# PCB_6.net
KiCad netlist of a schematic drawn in EAGLE
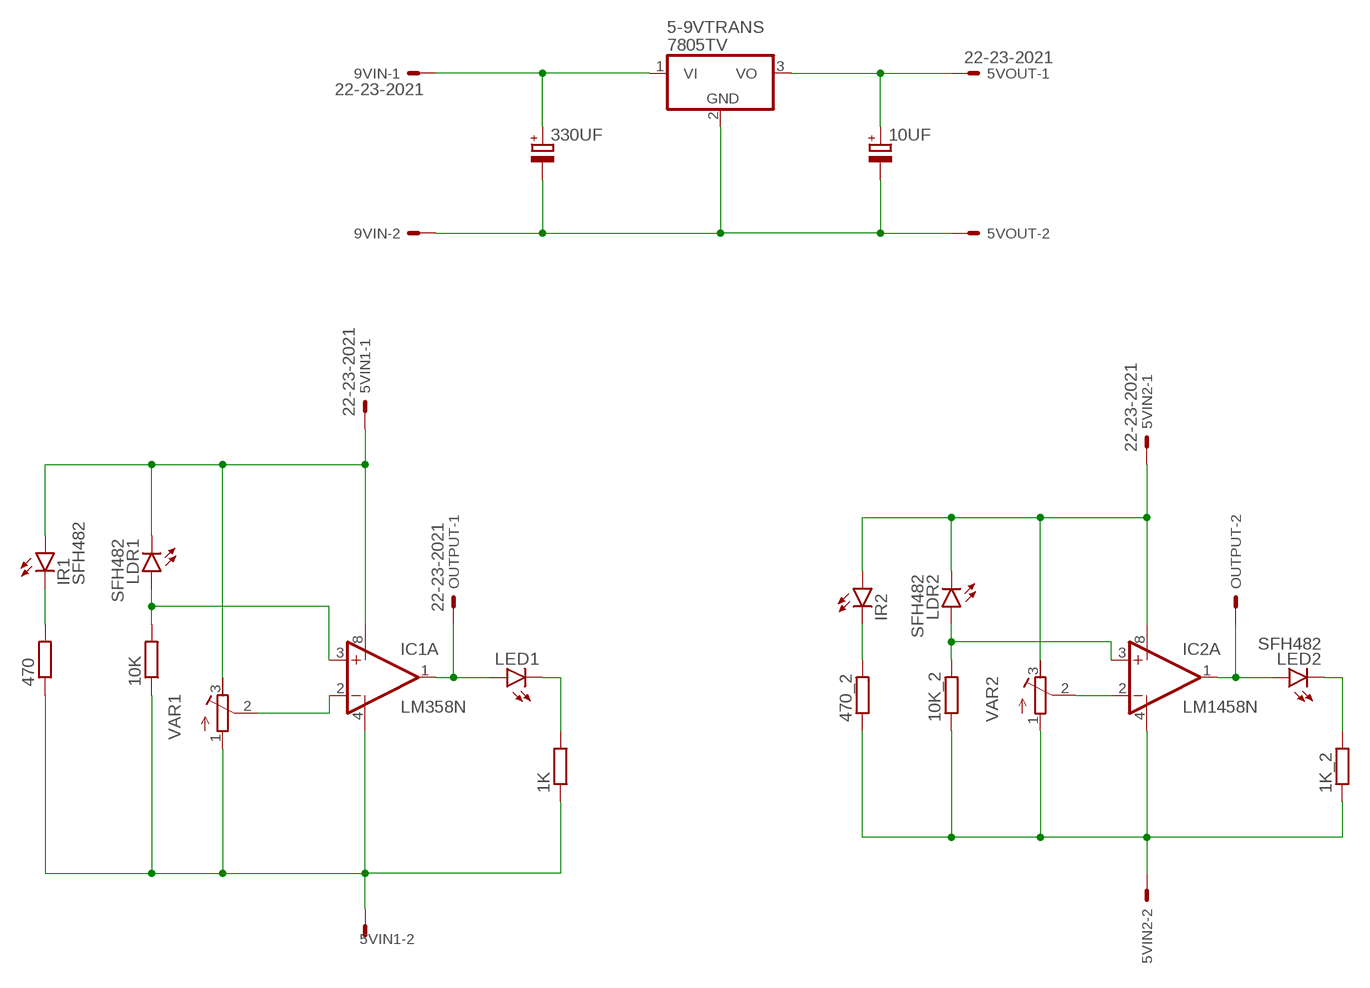
[diagram p0: schematic, sheet 1]

(export (version "E")
  (design (tool "Eeschema 10.0.6"))
  (components
    (comp (ref "1K")
      (value "R-EU_0207/10")
      (footprint "eagle-import:0207_10")
      (libsource (lib "eagle-import") (part "R-EU_0207/10"))
    )
    (comp (ref "1K_2")
      (value "R-EU_0207/10")
      (footprint "eagle-import:0207_10")
      (libsource (lib "eagle-import") (part "R-EU_0207/10"))
    )
    (comp (ref "5-9VTRANS")
      (value "7805TV")
      (footprint "eagle-import:TO220V")
      (libsource (lib "eagle-import") (part "78TV05"))
    )
    (comp (ref "5VIN1")
      (value "22-23-2021")
      (footprint "eagle-import:22-23-2021")
      (fields (field (name "MF") "MOLEX"))
      (libsource (lib "eagle-import") (part "22-23-2021"))
    )
    (comp (ref "5VIN2")
      (value "22-23-2021")
      (footprint "eagle-import:22-23-2021")
      (fields (field (name "MF") "MOLEX"))
      (libsource (lib "eagle-import") (part "22-23-2021"))
    )
    (comp (ref "5VOUT")
      (value "22-23-2021")
      (footprint "eagle-import:22-23-2021")
      (fields (field (name "MF") "MOLEX"))
      (libsource (lib "eagle-import") (part "22-23-2021"))
    )
    (comp (ref "9VIN")
      (value "22-23-2021")
      (footprint "eagle-import:22-23-2021")
      (fields (field (name "MF") "MOLEX"))
      (libsource (lib "eagle-import") (part "22-23-2021"))
    )
    (comp (ref "10K")
      (value "R-EU_0207/10")
      (footprint "eagle-import:0207_10")
      (libsource (lib "eagle-import") (part "R-EU_0207/10"))
    )
    (comp (ref "10K_2")
      (value "R-EU_0207/10")
      (footprint "eagle-import:0207_10")
      (libsource (lib "eagle-import") (part "R-EU_0207/10"))
    )
    (comp (ref "10UF")
      (value "CPOL-EUE1.8-4")
      (footprint "eagle-import:E1,8-4")
      (libsource (lib "eagle-import") (part "CPOL-EUE1.8-4"))
    )
    (comp (ref "330UF")
      (value "CPOL-EUE2,5-6E")
      (footprint "eagle-import:E2,5-6E")
      (libsource (lib "eagle-import") (part "CPOL-EUE2,5-6E"))
    )
    (comp (ref "470")
      (value "R-EU_0207/10")
      (footprint "eagle-import:0207_10")
      (libsource (lib "eagle-import") (part "R-EU_0207/10"))
    )
    (comp (ref "470_2")
      (value "R-EU_0207/10")
      (footprint "eagle-import:0207_10")
      (libsource (lib "eagle-import") (part "R-EU_0207/10"))
    )
    (comp (ref "IC1")
      (value "LM358N")
      (footprint "eagle-import:DIL08")
      (libsource (lib "eagle-import") (part "LM358N"))
    )
    (comp (ref "IC2")
      (value "LM1458N")
      (footprint "eagle-import:DIL08")
      (libsource (lib "eagle-import") (part "1458NLM"))
    )
    (comp (ref "IR1")
      (value "SFH482")
      (footprint "eagle-import:SFH482")
      (libsource (lib "eagle-import") (part "SFH482"))
    )
    (comp (ref "IR2")
      (value "LEDSFH480")
      (footprint "eagle-import:SFH480")
      (libsource (lib "eagle-import") (part "LEDSFH480"))
    )
    (comp (ref "LDR1")
      (value "SFH482")
      (footprint "eagle-import:SFH482")
      (libsource (lib "eagle-import") (part "SFH482"))
    )
    (comp (ref "LDR2")
      (value "SFH482")
      (footprint "eagle-import:SFH482")
      (libsource (lib "eagle-import") (part "SFH482"))
    )
    (comp (ref "LED1")
      (value "LEDSFH480")
      (footprint "eagle-import:SFH480")
      (libsource (lib "eagle-import") (part "LEDSFH480"))
    )
    (comp (ref "LED2")
      (value "SFH482")
      (footprint "eagle-import:SFH482")
      (libsource (lib "eagle-import") (part "SFH482"))
    )
    (comp (ref "OUTPUT")
      (value "22-23-2021")
      (footprint "eagle-import:22-23-2021")
      (fields (field (name "MF") "MOLEX"))
      (libsource (lib "eagle-import") (part "22-23-2021"))
    )
    (comp (ref "VAR1")
      (value "R-TRIMM64W")
      (footprint "eagle-import:RTRIM64W")
      (libsource (lib "eagle-import") (part "R-TRIMM64W"))
    )
    (comp (ref "VAR2")
      (value "R-TRIMM64W")
      (footprint "eagle-import:RTRIM64W")
      (libsource (lib "eagle-import") (part "R-TRIMM64W"))
    )
  )
  (nets
    (net (code "1") (name "Net-(5-9VTRANS-GND)") (class "Default")
      (node (ref "10UF") (pin "-") (pinfunction "-_-") (pintype "passive"))
      (node (ref "330UF") (pin "-") (pinfunction "-_-") (pintype "passive"))
      (node (ref "5-9VTRANS") (pin "2") (pinfunction "GND_2") (pintype "passive"))
      (node (ref "5VOUT") (pin "2") (pinfunction "S_2") (pintype "passive"))
      (node (ref "9VIN") (pin "2") (pinfunction "S_2") (pintype "passive"))
    )
    (net (code "2") (name "Net-(5-9VTRANS-VI)") (class "Default")
      (node (ref "330UF") (pin "+") (pinfunction "+_+") (pintype "passive"))
      (node (ref "5-9VTRANS") (pin "1") (pinfunction "VI_1") (pintype "input"))
      (node (ref "9VIN") (pin "1") (pinfunction "S_1") (pintype "passive"))
    )
    (net (code "3") (name "Net-(5-9VTRANS-VO)") (class "Default")
      (node (ref "10UF") (pin "+") (pinfunction "+_+") (pintype "passive"))
      (node (ref "5-9VTRANS") (pin "3") (pinfunction "VO_3") (pintype "passive"))
      (node (ref "5VOUT") (pin "1") (pinfunction "S_1") (pintype "passive"))
    )
    (net (code "4") (name "Net-(5VIN1A-S)") (class "Default")
      (node (ref "5VIN1") (pin "1") (pinfunction "S_1") (pintype "passive"))
      (node (ref "IC1") (pin "8") (pinfunction "V+_8") (pintype "power_in"))
      (node (ref "IR1") (pin "A") (pinfunction "A_A") (pintype "passive"))
      (node (ref "LDR1") (pin "K") (pinfunction "C_K") (pintype "passive"))
      (node (ref "VAR1") (pin "3") (pinfunction "E_3") (pintype "passive"))
    )
    (net (code "5") (name "Net-(5VIN1B-S)") (class "Default")
      (node (ref "10K") (pin "1") (pinfunction "1_1") (pintype "passive"))
      (node (ref "1K") (pin "1") (pinfunction "1_1") (pintype "passive"))
      (node (ref "470") (pin "1") (pinfunction "1_1") (pintype "passive"))
      (node (ref "5VIN1") (pin "2") (pinfunction "S_2") (pintype "passive"))
      (node (ref "IC1") (pin "4") (pinfunction "V-_4") (pintype "power_in"))
      (node (ref "VAR1") (pin "1") (pinfunction "A_1") (pintype "passive"))
    )
    (net (code "6") (name "Net-(5VIN2A-S)") (class "Default")
      (node (ref "5VIN2") (pin "1") (pinfunction "S_1") (pintype "passive"))
      (node (ref "IC2") (pin "8") (pinfunction "V+_8") (pintype "power_in"))
      (node (ref "IR2") (pin "A") (pinfunction "A_A") (pintype "passive"))
      (node (ref "LDR2") (pin "K") (pinfunction "C_K") (pintype "passive"))
      (node (ref "VAR2") (pin "3") (pinfunction "E_3") (pintype "passive"))
    )
    (net (code "7") (name "Net-(5VIN2B-S)") (class "Default")
      (node (ref "10K_2") (pin "1") (pinfunction "1_1") (pintype "passive"))
      (node (ref "1K_2") (pin "1") (pinfunction "1_1") (pintype "passive"))
      (node (ref "470_2") (pin "1") (pinfunction "1_1") (pintype "passive"))
      (node (ref "5VIN2") (pin "2") (pinfunction "S_2") (pintype "passive"))
      (node (ref "IC2") (pin "4") (pinfunction "V-_4") (pintype "power_in"))
      (node (ref "VAR2") (pin "1") (pinfunction "A_1") (pintype "passive"))
    )
    (net (code "8") (name "Net-(IC1A-+IN)") (class "Default")
      (node (ref "10K") (pin "2") (pinfunction "2_2") (pintype "passive"))
      (node (ref "IC1") (pin "3") (pinfunction "+IN_3") (pintype "input"))
      (node (ref "LDR1") (pin "A") (pinfunction "A_A") (pintype "passive"))
    )
    (net (code "9") (name "Net-(IC1A--IN)") (class "Default")
      (node (ref "IC1") (pin "2") (pinfunction "-IN_2") (pintype "input"))
      (node (ref "VAR1") (pin "2") (pinfunction "S_2") (pintype "passive"))
    )
    (net (code "10") (name "Net-(IC1A-OUT)") (class "Default")
      (node (ref "IC1") (pin "1") (pinfunction "OUT_1") (pintype "output"))
      (node (ref "LED1") (pin "A") (pinfunction "A_A") (pintype "passive"))
      (node (ref "OUTPUT") (pin "1") (pinfunction "S_1") (pintype "passive"))
    )
    (net (code "11") (name "Net-(IC2A-+IN)") (class "Default")
      (node (ref "10K_2") (pin "2") (pinfunction "2_2") (pintype "passive"))
      (node (ref "IC2") (pin "3") (pinfunction "+IN_3") (pintype "input"))
      (node (ref "LDR2") (pin "A") (pinfunction "A_A") (pintype "passive"))
    )
    (net (code "12") (name "Net-(IC2A--IN)") (class "Default")
      (node (ref "IC2") (pin "2") (pinfunction "-IN_2") (pintype "input"))
      (node (ref "VAR2") (pin "2") (pinfunction "S_2") (pintype "passive"))
    )
    (net (code "13") (name "Net-(IC2A-OUT)") (class "Default")
      (node (ref "IC2") (pin "1") (pinfunction "OUT_1") (pintype "output"))
      (node (ref "LED2") (pin "A") (pinfunction "A_A") (pintype "passive"))
      (node (ref "OUTPUT") (pin "2") (pinfunction "S_2") (pintype "passive"))
    )
    (net (code "14") (name "Net-(IR1-C)") (class "Default")
      (node (ref "470") (pin "2") (pinfunction "2_2") (pintype "passive"))
      (node (ref "IR1") (pin "K") (pinfunction "C_K") (pintype "passive"))
    )
    (net (code "15") (name "Net-(IR2-C)") (class "Default")
      (node (ref "470_2") (pin "2") (pinfunction "2_2") (pintype "passive"))
      (node (ref "IR2") (pin "K") (pinfunction "C_K") (pintype "passive"))
    )
    (net (code "16") (name "Net-(LED1-C)") (class "Default")
      (node (ref "1K") (pin "2") (pinfunction "2_2") (pintype "passive"))
      (node (ref "LED1") (pin "K") (pinfunction "C_K") (pintype "passive"))
    )
    (net (code "17") (name "Net-(LED2-C)") (class "Default")
      (node (ref "1K_2") (pin "2") (pinfunction "2_2") (pintype "passive"))
      (node (ref "LED2") (pin "K") (pinfunction "C_K") (pintype "passive"))
    )
  )
)
